# Source_TIA.net
KiCad netlist of a schematic drawn in Altium Designer
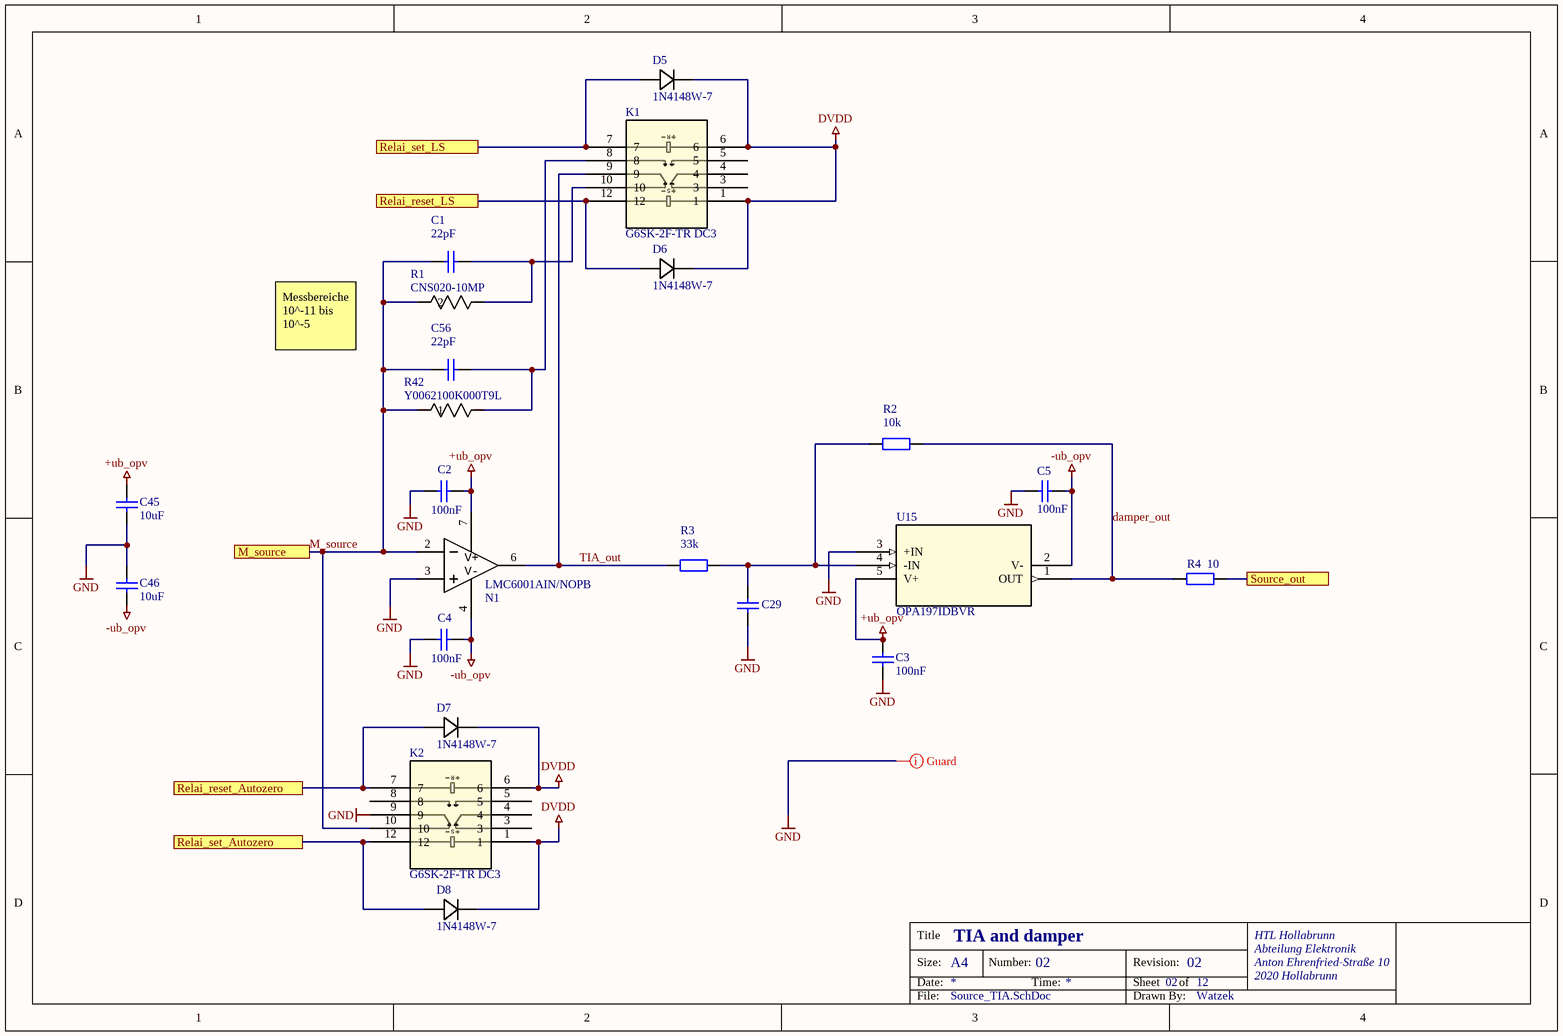
[diagram p0: Source_TIA.SchDoc]

(export (version "E")
  (design (tool "Eeschema 10.0.6"))
  (components
    (comp (ref "C1")
      (value "22pF")
      (footprint "C1206-KUE")
      (description "Capacitor")
      (fields (field (name "MANUFACTURER") "Kemet") (field (name "PUBLISHER") "Altium Limited"))
      (libsource (lib "ExtrapartsKUE_V01") (part "Capacitor"))
    )
    (comp (ref "C2")
      (value "100nF")
      (footprint "C1206-KUE")
      (description "Capacitor")
      (fields (field (name "MANUFACTURER") "Kemet") (field (name "PUBLISHER") "Altium Limited"))
      (libsource (lib "ExtrapartsKUE_V01") (part "Capacitor"))
    )
    (comp (ref "C3")
      (value "100nF")
      (footprint "C1206-KUE")
      (description "Capacitor")
      (fields (field (name "MANUFACTURER") "Kemet") (field (name "PUBLISHER") "Altium Limited"))
      (libsource (lib "ExtrapartsKUE_V01") (part "Capacitor"))
    )
    (comp (ref "C4")
      (value "100nF")
      (footprint "C1206-KUE")
      (description "Capacitor")
      (fields (field (name "MANUFACTURER") "Kemet") (field (name "PUBLISHER") "Altium Limited"))
      (libsource (lib "ExtrapartsKUE_V01") (part "Capacitor"))
    )
    (comp (ref "C5")
      (value "100nF")
      (footprint "C1206-KUE")
      (description "Capacitor")
      (fields (field (name "MANUFACTURER") "Kemet") (field (name "PUBLISHER") "Altium Limited"))
      (libsource (lib "ExtrapartsKUE_V01") (part "Capacitor"))
    )
    (comp (ref "C29")
      (value "~")
      (footprint "C1206-KUE")
      (description "Capacitor")
      (fields (field (name "MANUFACTURER") "Kemet") (field (name "PUBLISHER") "Altium Limited"))
      (libsource (lib "ExtrapartsKUE_V01") (part "Capacitor"))
    )
    (comp (ref "C45")
      (value "10uF")
      (footprint "C1206-KUE")
      (description "Capacitor")
      (fields (field (name "MANUFACTURER") "Kemet") (field (name "PUBLISHER") "Altium Limited"))
      (libsource (lib "ExtrapartsKUE_V01") (part "Capacitor"))
    )
    (comp (ref "C46")
      (value "10uF")
      (footprint "C1206-KUE")
      (description "Capacitor")
      (fields (field (name "MANUFACTURER") "Kemet") (field (name "PUBLISHER") "Altium Limited"))
      (libsource (lib "ExtrapartsKUE_V01") (part "Capacitor"))
    )
    (comp (ref "C56")
      (value "22pF")
      (footprint "C1206-KUE")
      (description "Capacitor")
      (fields (field (name "MANUFACTURER") "Kemet") (field (name "PUBLISHER") "Altium Limited"))
      (libsource (lib "ExtrapartsKUE_V01") (part "Capacitor"))
    )
    (comp (ref "D5")
      (value "1N4148W-7")
      (footprint "SOD123_DIO")
      (description "Description")
      (fields (field (name "COPYRIGHT") "Copyright (C) 2026 Ultra Librarian. All rights reserved."))
      (libsource (lib "1N4148W-7") (part "1N4148W-7"))
    )
    (comp (ref "D6")
      (value "1N4148W-7")
      (footprint "SOD123_DIO")
      (description "Description")
      (fields (field (name "COPYRIGHT") "Copyright (C) 2026 Ultra Librarian. All rights reserved."))
      (libsource (lib "1N4148W-7") (part "1N4148W-7"))
    )
    (comp (ref "D7")
      (value "1N4148W-7")
      (footprint "SOD123_DIO")
      (description "Description")
      (fields (field (name "COPYRIGHT") "Copyright (C) 2026 Ultra Librarian. All rights reserved."))
      (libsource (lib "1N4148W-7") (part "1N4148W-7"))
    )
    (comp (ref "D8")
      (value "1N4148W-7")
      (footprint "SOD123_DIO")
      (description "Description")
      (fields (field (name "COPYRIGHT") "Copyright (C) 2026 Ultra Librarian. All rights reserved."))
      (libsource (lib "1N4148W-7") (part "1N4148W-7"))
    )
    (comp (ref "K1")
      (value "G6SK-2F-TR DC3")
      (footprint "RELAY_G6SK-2F DC3_OMR")
      (description "Description")
      (fields (field (name "COPYRIGHT") "Copyright (C) 2026 Ultra Librarian. All rights reserved."))
      (libsource (lib "G6SK-2F-TRDC3") (part "G6SK-2F-TR DC3"))
    )
    (comp (ref "K2")
      (value "G6SK-2F-TR DC3")
      (footprint "RELAY_G6SK-2F DC3_OMR")
      (description "Description")
      (fields (field (name "COPYRIGHT") "Copyright (C) 2026 Ultra Librarian. All rights reserved."))
      (libsource (lib "G6SK-2F-TRDC3") (part "G6SK-2F-TR DC3"))
    )
    (comp (ref "N1")
      (value "LMC6001AIN/NOPB")
      (footprint "DIP8")
      (description "Ultra-Low Input Current Amplifier 8-PDIP -40 to 85")
      (fields
        (field (name "PARTNUMBER") "LMC6001AIN")
        (field (name "MANUFACTURER") "NationalSemiconductor")
        (field (name "COPYRIGHT") "Copyright (C) 2025 Ultra Librarian. All rights reserved.")
        (field (name "PUBLISHER") "NationalSemiconductor")
      )
      (libsource (lib "MyOwnParts") (part "LMC6001AINNOPB"))
    )
    (comp (ref "R1")
      (value "CNS020-10MP")
      (footprint "RES_CNS020_VIS")
      (description "CNS 020 10K 0,02% e2")
      (fields
        (field (name "MANUFACTURER_PART_NUMBER") "CNS020-10KP")
        (field (name "COPYRIGHT") "Copyright (C) 2026 Ultra Librarian. All rights reserved.")
      )
      (libsource (lib "MyOwnParts") (part "CNS020-10KP"))
    )
    (comp (ref "R2")
      (value "10k")
      (footprint "C1206-KUE")
      (description "Resistor SMD")
      (fields (field (name "MANUFACTURER") "AVX") (field (name "PUBLISHER") "Altium Limited"))
      (libsource (lib "ExtrapartsKUE_V01") (part "ResistorSMD"))
    )
    (comp (ref "R3")
      (value "33k")
      (footprint "C1206-KUE")
      (description "Resistor SMD")
      (fields (field (name "MANUFACTURER") "AVX") (field (name "PUBLISHER") "Altium Limited"))
      (libsource (lib "ExtrapartsKUE_V01") (part "ResistorSMD"))
    )
    (comp (ref "R4")
      (value "10")
      (footprint "C1206-KUE")
      (description "Resistor SMD")
      (fields (field (name "MANUFACTURER") "AVX") (field (name "PUBLISHER") "Altium Limited"))
      (libsource (lib "ExtrapartsKUE_V01") (part "ResistorSMD"))
    )
    (comp (ref "R42")
      (value "Y0062100K000T9L")
      (footprint "RES_S102K_7P62X2P67_VIS")
      (description "No Description Available")
      (fields (field (name "COPYRIGHT") "Copyright (C) 2026 Ultra Librarian. All rights reserved."))
      (libsource (lib "Y0062100K000T9L") (part "Y0062100K000T9L"))
    )
    (comp (ref "U15")
      (value "OPA197IDBVR")
      (footprint "DBV5_TEX")
      (description "Single, 36-V, precision, rail-to-rail input output, low offset voltage op amp 5-SOT-23 -40 to 125")
      (fields (field (name "COPYRIGHT") "Copyright (C) 2025 Ultra Librarian. All rights reserved."))
      (libsource (lib "OPA197IDBVR") (part "OPA197IDBVR"))
    )
  )
  (nets
    (net (code "1") (name "+ub_opv") (class "Default")
      (node (ref "C2") (pin "2") (pinfunction "2_2") (pintype "passive"))
      (node (ref "C3") (pin "2") (pinfunction "2_2") (pintype "passive"))
      (node (ref "C45") (pin "2") (pinfunction "2_2") (pintype "passive"))
      (node (ref "N1") (pin "7") (pinfunction "V+_7") (pintype "power_in"))
      (node (ref "U15") (pin "5") (pinfunction "V+_5") (pintype "power_in"))
    )
    (net (code "2") (name "-ub_opv") (class "Default")
      (node (ref "C4") (pin "2") (pinfunction "2_2") (pintype "passive"))
      (node (ref "C46") (pin "1") (pinfunction "1_1") (pintype "passive"))
      (node (ref "C5") (pin "2") (pinfunction "2_2") (pintype "passive"))
      (node (ref "N1") (pin "4") (pinfunction "V-_4") (pintype "power_in"))
      (node (ref "U15") (pin "2") (pinfunction "V-_2") (pintype "power_in"))
    )
    (net (code "3") (name "/M_source") (class "Default")
      (node (ref "C1") (pin "1") (pinfunction "1_1") (pintype "passive"))
      (node (ref "C56") (pin "1") (pinfunction "1_1") (pintype "passive"))
      (node (ref "K2") (pin "10") (pinfunction "10_10") (pintype "passive"))
      (node (ref "N1") (pin "2") (pinfunction "IN-_2") (pintype "passive"))
      (node (ref "R1") (pin "2") (pinfunction "2_2") (pintype "passive"))
      (node (ref "R42") (pin "1") (pinfunction "1_1") (pintype "passive"))
    )
    (net (code "4") (name "/Relai_reset_Autozero") (class "Default")
      (node (ref "D7") (pin "2") (pinfunction "2_2") (pintype "passive"))
      (node (ref "K2") (pin "7") (pinfunction "7_7") (pintype "passive"))
    )
    (net (code "5") (name "/Relai_reset_LS") (class "Default")
      (node (ref "D6") (pin "2") (pinfunction "2_2") (pintype "passive"))
      (node (ref "K1") (pin "12") (pinfunction "12_12") (pintype "passive"))
    )
    (net (code "6") (name "/Relai_set_Autozero") (class "Default")
      (node (ref "D8") (pin "2") (pinfunction "2_2") (pintype "passive"))
      (node (ref "K2") (pin "12") (pinfunction "12_12") (pintype "passive"))
    )
    (net (code "7") (name "/Relai_set_LS") (class "Default")
      (node (ref "D5") (pin "2") (pinfunction "2_2") (pintype "passive"))
      (node (ref "K1") (pin "7") (pinfunction "7_7") (pintype "passive"))
    )
    (net (code "8") (name "/Source_out") (class "Default")
      (node (ref "R4") (pin "1") (pinfunction "1_1") (pintype "passive"))
    )
    (net (code "9") (name "/TIA_out") (class "Default")
      (node (ref "K1") (pin "9") (pinfunction "9_9") (pintype "passive"))
      (node (ref "N1") (pin "6") (pinfunction "OUT_6") (pintype "passive"))
      (node (ref "R3") (pin "2") (pinfunction "2_2") (pintype "passive"))
    )
    (net (code "10") (name "/damper_out") (class "Default")
      (node (ref "R2") (pin "1") (pinfunction "1_1") (pintype "passive"))
      (node (ref "R4") (pin "2") (pinfunction "2_2") (pintype "passive"))
      (node (ref "U15") (pin "1") (pinfunction "OUT_1") (pintype "output"))
    )
    (net (code "11") (name "DVDD") (class "Default")
      (node (ref "D5") (pin "1") (pinfunction "1_1") (pintype "passive"))
      (node (ref "D6") (pin "1") (pinfunction "1_1") (pintype "passive"))
      (node (ref "D7") (pin "1") (pinfunction "1_1") (pintype "passive"))
      (node (ref "D8") (pin "1") (pinfunction "1_1") (pintype "passive"))
      (node (ref "K1") (pin "1") (pinfunction "1_1") (pintype "passive"))
      (node (ref "K1") (pin "6") (pinfunction "6_6") (pintype "passive"))
      (node (ref "K2") (pin "1") (pinfunction "1_1") (pintype "passive"))
      (node (ref "K2") (pin "6") (pinfunction "6_6") (pintype "passive"))
    )
    (net (code "12") (name "GND") (class "Default")
      (node (ref "C2") (pin "1") (pinfunction "1_1") (pintype "passive"))
      (node (ref "C29") (pin "1") (pinfunction "1_1") (pintype "passive"))
      (node (ref "C3") (pin "1") (pinfunction "1_1") (pintype "passive"))
      (node (ref "C4") (pin "1") (pinfunction "1_1") (pintype "passive"))
      (node (ref "C45") (pin "1") (pinfunction "1_1") (pintype "passive"))
      (node (ref "C46") (pin "2") (pinfunction "2_2") (pintype "passive"))
      (node (ref "C5") (pin "1") (pinfunction "1_1") (pintype "passive"))
      (node (ref "K2") (pin "9") (pinfunction "9_9") (pintype "passive"))
      (node (ref "N1") (pin "3") (pinfunction "IN+_3") (pintype "passive"))
      (node (ref "U15") (pin "3") (pinfunction "+IN_3") (pintype "input"))
    )
    (net (code "13") (name "Net-(C1-Pad2)") (class "Default")
      (node (ref "C1") (pin "2") (pinfunction "2_2") (pintype "passive"))
      (node (ref "K1") (pin "10") (pinfunction "10_10") (pintype "passive"))
      (node (ref "R1") (pin "1") (pinfunction "1_1") (pintype "passive"))
    )
    (net (code "14") (name "Net-(C56-Pad2)") (class "Default")
      (node (ref "C56") (pin "2") (pinfunction "2_2") (pintype "passive"))
      (node (ref "K1") (pin "8") (pinfunction "8_8") (pintype "passive"))
      (node (ref "R42") (pin "2") (pinfunction "2_2") (pintype "passive"))
    )
    (net (code "15") (name "Net-(U15--IN)") (class "Default")
      (node (ref "C29") (pin "2") (pinfunction "2_2") (pintype "passive"))
      (node (ref "R2") (pin "2") (pinfunction "2_2") (pintype "passive"))
      (node (ref "R3") (pin "1") (pinfunction "1_1") (pintype "passive"))
      (node (ref "U15") (pin "4") (pinfunction "-IN_4") (pintype "input"))
    )
    (net (code "16") (name "unconnected-(K1-Pad3)") (class "Default")
      (node (ref "K1") (pin "3") (pinfunction "3_3") (pintype "passive"))
    )
    (net (code "17") (name "unconnected-(K1-Pad4)") (class "Default")
      (node (ref "K1") (pin "4") (pinfunction "4_4") (pintype "passive"))
    )
    (net (code "18") (name "unconnected-(K1-Pad5)") (class "Default")
      (node (ref "K1") (pin "5") (pinfunction "5_5") (pintype "passive"))
    )
    (net (code "19") (name "unconnected-(K2-Pad3)") (class "Default")
      (node (ref "K2") (pin "3") (pinfunction "3_3") (pintype "passive"))
    )
    (net (code "20") (name "unconnected-(K2-Pad4)") (class "Default")
      (node (ref "K2") (pin "4") (pinfunction "4_4") (pintype "passive"))
    )
    (net (code "21") (name "unconnected-(K2-Pad5)") (class "Default")
      (node (ref "K2") (pin "5") (pinfunction "5_5") (pintype "passive"))
    )
    (net (code "22") (name "unconnected-(K2-Pad8)") (class "Default")
      (node (ref "K2") (pin "8") (pinfunction "8_8") (pintype "passive"))
    )
  )
)
